# alfie2.net
KiCad netlist of a schematic drawn in EAGLE
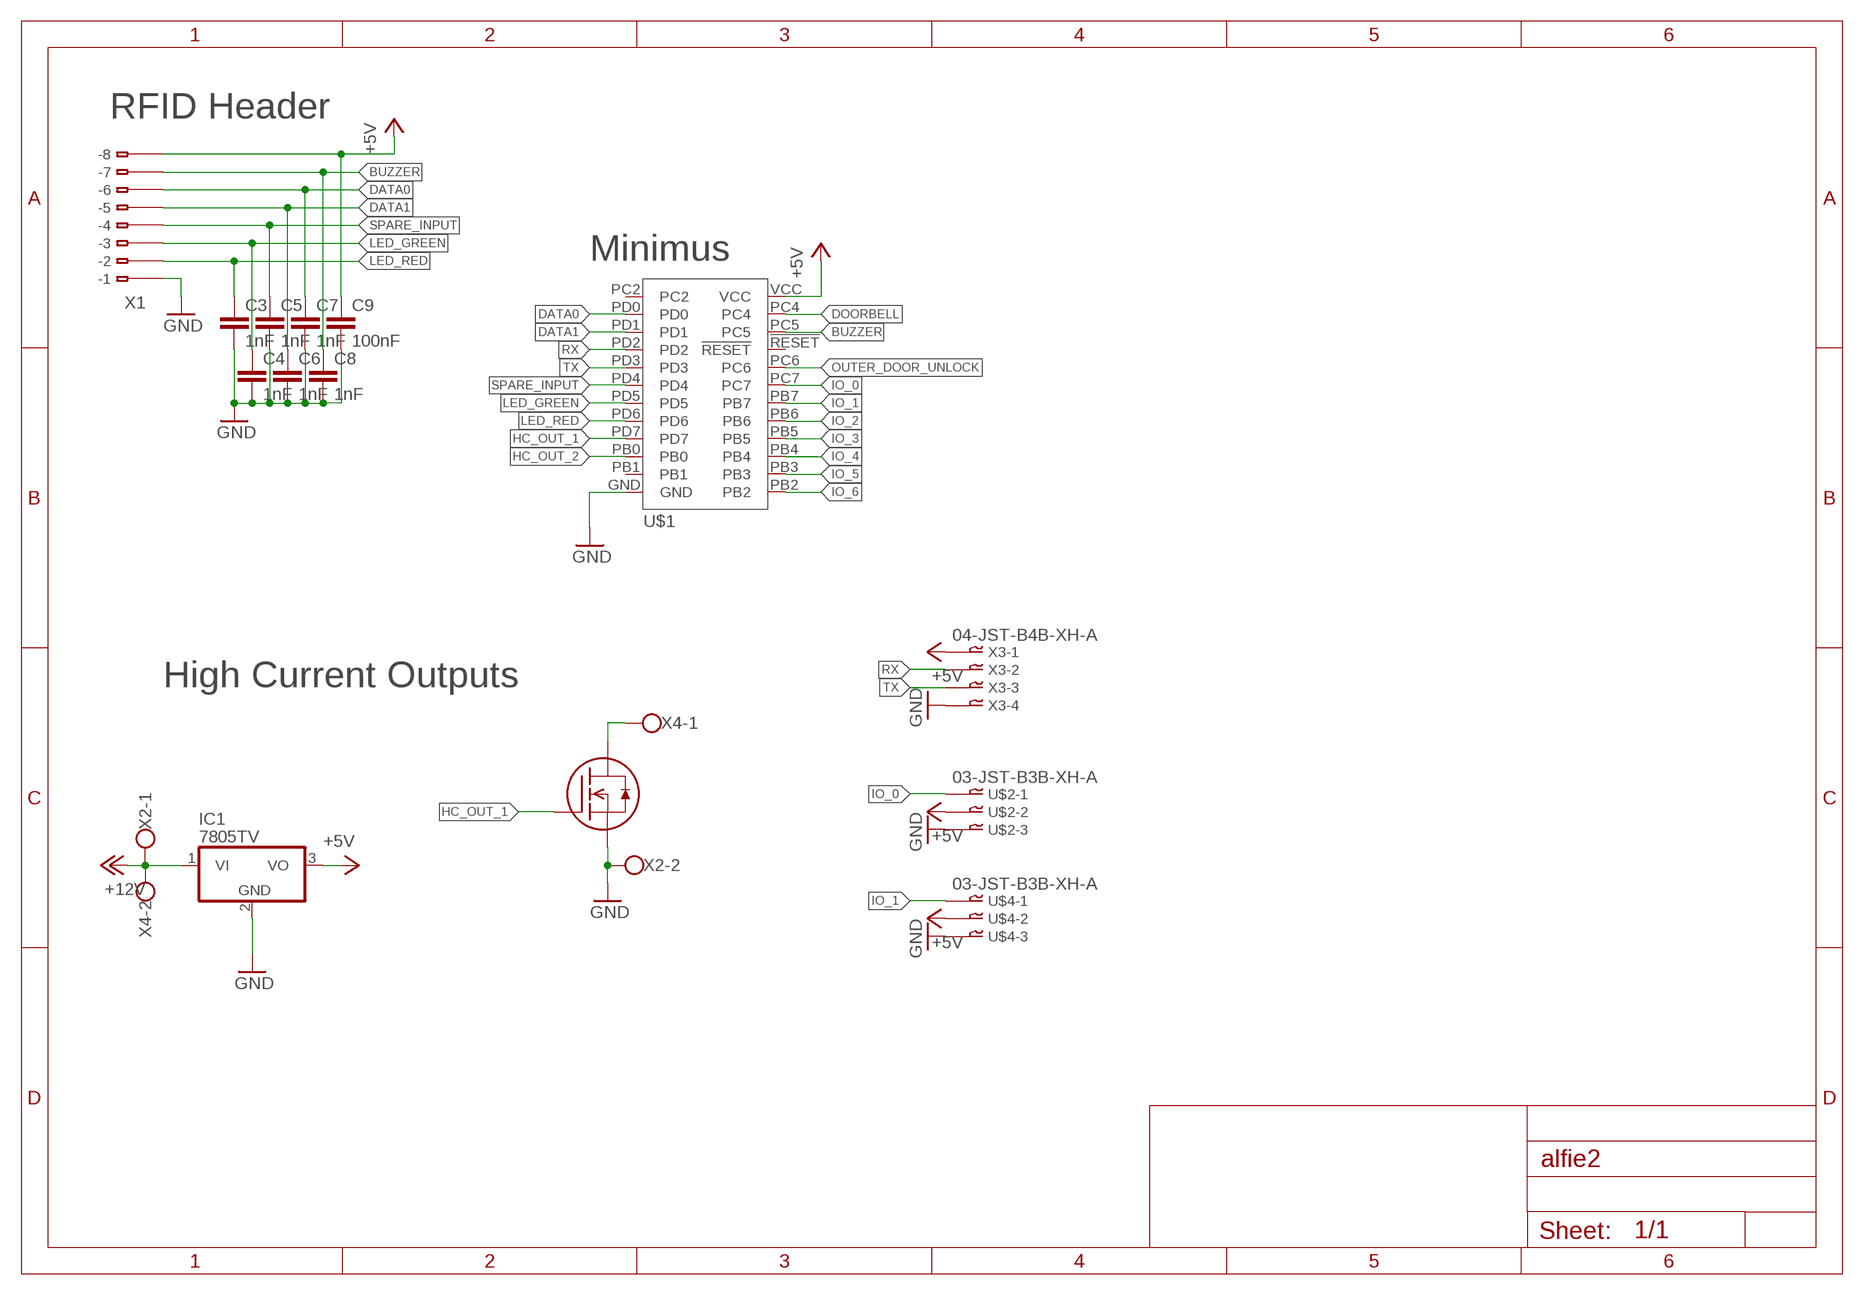
[diagram p0: schematic, sheet 1]

(export (version "E")
  (design (tool "Eeschema 10.0.6"))
  (components
    (comp (ref "C3")
      (value "1nF")
      (footprint "eagle-import:C0805")
      (libsource (lib "eagle-import") (part "C-EUC0805"))
    )
    (comp (ref "C4")
      (value "1nF")
      (footprint "eagle-import:C0805")
      (libsource (lib "eagle-import") (part "C-EUC0805"))
    )
    (comp (ref "C5")
      (value "1nF")
      (footprint "eagle-import:C0805")
      (libsource (lib "eagle-import") (part "C-EUC0805"))
    )
    (comp (ref "C6")
      (value "1nF")
      (footprint "eagle-import:C0805")
      (libsource (lib "eagle-import") (part "C-EUC0805"))
    )
    (comp (ref "C7")
      (value "1nF")
      (footprint "eagle-import:C0805")
      (libsource (lib "eagle-import") (part "C-EUC0805"))
    )
    (comp (ref "C8")
      (value "1nF")
      (footprint "eagle-import:C0805")
      (libsource (lib "eagle-import") (part "C-EUC0805"))
    )
    (comp (ref "C9")
      (value "100nF")
      (footprint "eagle-import:C0805")
      (libsource (lib "eagle-import") (part "C-EUC0805"))
    )
    (comp (ref "IC1")
      (value "7805TV")
      (footprint "eagle-import:TO220V")
      (libsource (lib "eagle-import") (part "78TV05"))
    )
    (comp (ref "U$1")
      (value "MINIMUS")
      (footprint "eagle-import:MINIMUS")
      (libsource (lib "eagle-import") (part "MINIMUS"))
    )
    (comp (ref "U$2")
      (value "03-JST-B3B-XH-A")
      (footprint "eagle-import:B3B-XH")
      (libsource (lib "eagle-import") (part "03-JST-B3B-XH-A"))
    )
    (comp (ref "U$3")
      (value "NTF3055L108T1GTAB")
      (footprint "eagle-import:SOT223")
      (libsource (lib "eagle-import") (part "NTF3055L108T1GTAB"))
    )
    (comp (ref "U$4")
      (value "03-JST-B3B-XH-A")
      (footprint "eagle-import:B3B-XH")
      (libsource (lib "eagle-import") (part "03-JST-B3B-XH-A"))
    )
    (comp (ref "X1")
      (value "233-508")
      (footprint "eagle-import:233-508")
      (fields (field (name "MF") "Wago Corporation") (field (name "MPN") "0233-0508"))
      (libsource (lib "eagle-import") (part "233-508"))
    )
    (comp (ref "X2")
      (value "W237-102")
      (footprint "eagle-import:W237-102")
      (fields (field (name "MPN") "237-102"))
      (libsource (lib "eagle-import") (part "W237-102"))
    )
    (comp (ref "X3")
      (value "04-JST-B4B-XH-A")
      (footprint "eagle-import:B4B-XH")
      (libsource (lib "eagle-import") (part "04-JST-B4B-XH-A"))
    )
    (comp (ref "X4")
      (value "W237-102")
      (footprint "eagle-import:W237-102")
      (fields (field (name "MPN") "237-102"))
      (libsource (lib "eagle-import") (part "W237-102"))
    )
  )
  (nets
    (net (code "1") (name "+5V") (class "Default")
      (node (ref "C9") (pin "1") (pinfunction "1_1") (pintype "passive"))
      (node (ref "IC1") (pin "3") (pinfunction "VO_3") (pintype "passive"))
      (node (ref "U$1") (pin "VCC") (pinfunction "VCC_VCC") (pintype "power_in"))
      (node (ref "U$2") (pin "P$2") (pinfunction "1_P$2") (pintype "passive"))
      (node (ref "U$4") (pin "P$2") (pinfunction "1_P$2") (pintype "passive"))
      (node (ref "X1") (pin "B8") (pinfunction "B-8_B8") (pintype "passive"))
      (node (ref "X3") (pin "P$1") (pinfunction "1_P$1") (pintype "passive"))
    )
    (net (code "2") (name "+12V") (class "Default")
      (node (ref "IC1") (pin "1") (pinfunction "VI_1") (pintype "input"))
      (node (ref "X2") (pin "1") (pinfunction "KL_1") (pintype "passive"))
      (node (ref "X4") (pin "2") (pinfunction "KL_2") (pintype "passive"))
    )
    (net (code "3") (name "BUZZER") (class "Default")
      (node (ref "C8") (pin "1") (pinfunction "1_1") (pintype "passive"))
      (node (ref "U$1") (pin "PC5") (pinfunction "PC5_PC5") (pintype "bidirectional"))
      (node (ref "X1") (pin "B7") (pinfunction "B-7_B7") (pintype "passive"))
    )
    (net (code "4") (name "DATA0") (class "Default")
      (node (ref "C7") (pin "1") (pinfunction "1_1") (pintype "passive"))
      (node (ref "U$1") (pin "PD0") (pinfunction "PD0_PD0") (pintype "bidirectional"))
      (node (ref "X1") (pin "B6") (pinfunction "B-6_B6") (pintype "passive"))
    )
    (net (code "5") (name "DATA1") (class "Default")
      (node (ref "C6") (pin "1") (pinfunction "1_1") (pintype "passive"))
      (node (ref "U$1") (pin "PD1") (pinfunction "PD1_PD1") (pintype "bidirectional"))
      (node (ref "X1") (pin "B5") (pinfunction "B-5_B5") (pintype "passive"))
    )
    (net (code "6") (name "DOORBELL") (class "Default")
      (node (ref "U$1") (pin "PC4") (pinfunction "PC4_PC4") (pintype "bidirectional"))
    )
    (net (code "7") (name "GND") (class "Default")
      (node (ref "C3") (pin "2") (pinfunction "2_2") (pintype "passive"))
      (node (ref "C4") (pin "2") (pinfunction "2_2") (pintype "passive"))
      (node (ref "C5") (pin "2") (pinfunction "2_2") (pintype "passive"))
      (node (ref "C6") (pin "2") (pinfunction "2_2") (pintype "passive"))
      (node (ref "C7") (pin "2") (pinfunction "2_2") (pintype "passive"))
      (node (ref "C8") (pin "2") (pinfunction "2_2") (pintype "passive"))
      (node (ref "C9") (pin "2") (pinfunction "2_2") (pintype "passive"))
      (node (ref "IC1") (pin "2") (pinfunction "GND_2") (pintype "passive"))
      (node (ref "U$1") (pin "GND") (pinfunction "GND_GND") (pintype "power_in"))
      (node (ref "U$2") (pin "P$3") (pinfunction "1_P$3") (pintype "passive"))
      (node (ref "U$3") (pin "3") (pinfunction "S_3") (pintype "passive"))
      (node (ref "U$4") (pin "P$3") (pinfunction "1_P$3") (pintype "passive"))
      (node (ref "X1") (pin "B1") (pinfunction "B-1_B1") (pintype "passive"))
      (node (ref "X2") (pin "2") (pinfunction "KL_2") (pintype "passive"))
      (node (ref "X3") (pin "P$4") (pinfunction "1_P$4") (pintype "passive"))
    )
    (net (code "8") (name "HC_OUT_1") (class "Default")
      (node (ref "U$1") (pin "PD7") (pinfunction "PD7_PD7") (pintype "bidirectional"))
      (node (ref "U$3") (pin "1") (pinfunction "G_1") (pintype "passive"))
    )
    (net (code "9") (name "HC_OUT_2") (class "Default")
      (node (ref "U$1") (pin "PB0") (pinfunction "PB0_PB0") (pintype "bidirectional"))
    )
    (net (code "10") (name "IO_0") (class "Default")
      (node (ref "U$1") (pin "PC7") (pinfunction "PC7_PC7") (pintype "bidirectional"))
      (node (ref "U$2") (pin "P$1") (pinfunction "1_P$1") (pintype "passive"))
    )
    (net (code "11") (name "IO_1") (class "Default")
      (node (ref "U$1") (pin "PB7") (pinfunction "PB7_PB7") (pintype "bidirectional"))
      (node (ref "U$4") (pin "P$1") (pinfunction "1_P$1") (pintype "passive"))
    )
    (net (code "12") (name "IO_2") (class "Default")
      (node (ref "U$1") (pin "PB6") (pinfunction "PB6_PB6") (pintype "bidirectional"))
    )
    (net (code "13") (name "IO_3") (class "Default")
      (node (ref "U$1") (pin "PB5") (pinfunction "PB5_PB5") (pintype "bidirectional"))
    )
    (net (code "14") (name "IO_4") (class "Default")
      (node (ref "U$1") (pin "PB4") (pinfunction "PB4_PB4") (pintype "bidirectional"))
    )
    (net (code "15") (name "IO_5") (class "Default")
      (node (ref "U$1") (pin "PB3") (pinfunction "PB3_PB3") (pintype "bidirectional"))
    )
    (net (code "16") (name "IO_6") (class "Default")
      (node (ref "U$1") (pin "PB2") (pinfunction "PB2_PB2") (pintype "bidirectional"))
    )
    (net (code "17") (name "LED_GREEN") (class "Default")
      (node (ref "C4") (pin "1") (pinfunction "1_1") (pintype "passive"))
      (node (ref "U$1") (pin "PD5") (pinfunction "PD5_PD5") (pintype "bidirectional"))
      (node (ref "X1") (pin "B3") (pinfunction "B-3_B3") (pintype "passive"))
    )
    (net (code "18") (name "LED_RED") (class "Default")
      (node (ref "C3") (pin "1") (pinfunction "1_1") (pintype "passive"))
      (node (ref "U$1") (pin "PD6") (pinfunction "PD6_PD6") (pintype "bidirectional"))
      (node (ref "X1") (pin "B2") (pinfunction "B-2_B2") (pintype "passive"))
    )
    (net (code "19") (name "Net-(U$3-D)") (class "Default")
      (node (ref "U$3") (pin "4") (pinfunction "D_4") (pintype "passive"))
      (node (ref "X4") (pin "1") (pinfunction "KL_1") (pintype "passive"))
    )
    (net (code "20") (name "OUTER_DOOR_UNLOCK") (class "Default")
      (node (ref "U$1") (pin "PC6") (pinfunction "PC6_PC6") (pintype "bidirectional"))
    )
    (net (code "21") (name "RX") (class "Default")
      (node (ref "U$1") (pin "PD2") (pinfunction "PD2_PD2") (pintype "bidirectional"))
      (node (ref "X3") (pin "P$2") (pinfunction "1_P$2") (pintype "passive"))
    )
    (net (code "22") (name "SPARE_INPUT") (class "Default")
      (node (ref "C5") (pin "1") (pinfunction "1_1") (pintype "passive"))
      (node (ref "U$1") (pin "PD4") (pinfunction "PD4_PD4") (pintype "bidirectional"))
      (node (ref "X1") (pin "B4") (pinfunction "B-4_B4") (pintype "passive"))
    )
    (net (code "23") (name "TX") (class "Default")
      (node (ref "U$1") (pin "PD3") (pinfunction "PD3_PD3") (pintype "bidirectional"))
      (node (ref "X3") (pin "P$3") (pinfunction "1_P$3") (pintype "passive"))
    )
    (net (code "24") (name "unconnected-(U$1-PadPB1)") (class "Default")
      (node (ref "U$1") (pin "PB1") (pinfunction "PB1_PB1") (pintype "bidirectional"))
    )
    (net (code "25") (name "unconnected-(U$1-PadPC2)") (class "Default")
      (node (ref "U$1") (pin "PC2") (pinfunction "PC2_PC2") (pintype "bidirectional"))
    )
    (net (code "26") (name "unconnected-(U$1-~{RESET}-Pad!RESET)") (class "Default")
      (node (ref "U$1") (pin "!RESET") (pinfunction "~{RESET}_!RESET") (pintype "input"))
    )
    (net (code "27") (name "unconnected-(X1--1-PadA1)") (class "Default")
      (node (ref "X1") (pin "A1") (pinfunction "-1_A1") (pintype "passive"))
    )
    (net (code "28") (name "unconnected-(X1--2-PadA2)") (class "Default")
      (node (ref "X1") (pin "A2") (pinfunction "-2_A2") (pintype "passive"))
    )
    (net (code "29") (name "unconnected-(X1--3-PadA3)") (class "Default")
      (node (ref "X1") (pin "A3") (pinfunction "-3_A3") (pintype "passive"))
    )
    (net (code "30") (name "unconnected-(X1--4-PadA4)") (class "Default")
      (node (ref "X1") (pin "A4") (pinfunction "-4_A4") (pintype "passive"))
    )
    (net (code "31") (name "unconnected-(X1--5-PadA5)") (class "Default")
      (node (ref "X1") (pin "A5") (pinfunction "-5_A5") (pintype "passive"))
    )
    (net (code "32") (name "unconnected-(X1--6-PadA6)") (class "Default")
      (node (ref "X1") (pin "A6") (pinfunction "-6_A6") (pintype "passive"))
    )
    (net (code "33") (name "unconnected-(X1--7-PadA7)") (class "Default")
      (node (ref "X1") (pin "A7") (pinfunction "-7_A7") (pintype "passive"))
    )
    (net (code "34") (name "unconnected-(X1--8-PadA8)") (class "Default")
      (node (ref "X1") (pin "A8") (pinfunction "-8_A8") (pintype "passive"))
    )
  )
)
